# 06_LAN7800.net
KiCad netlist of a schematic drawn in Altium Designer
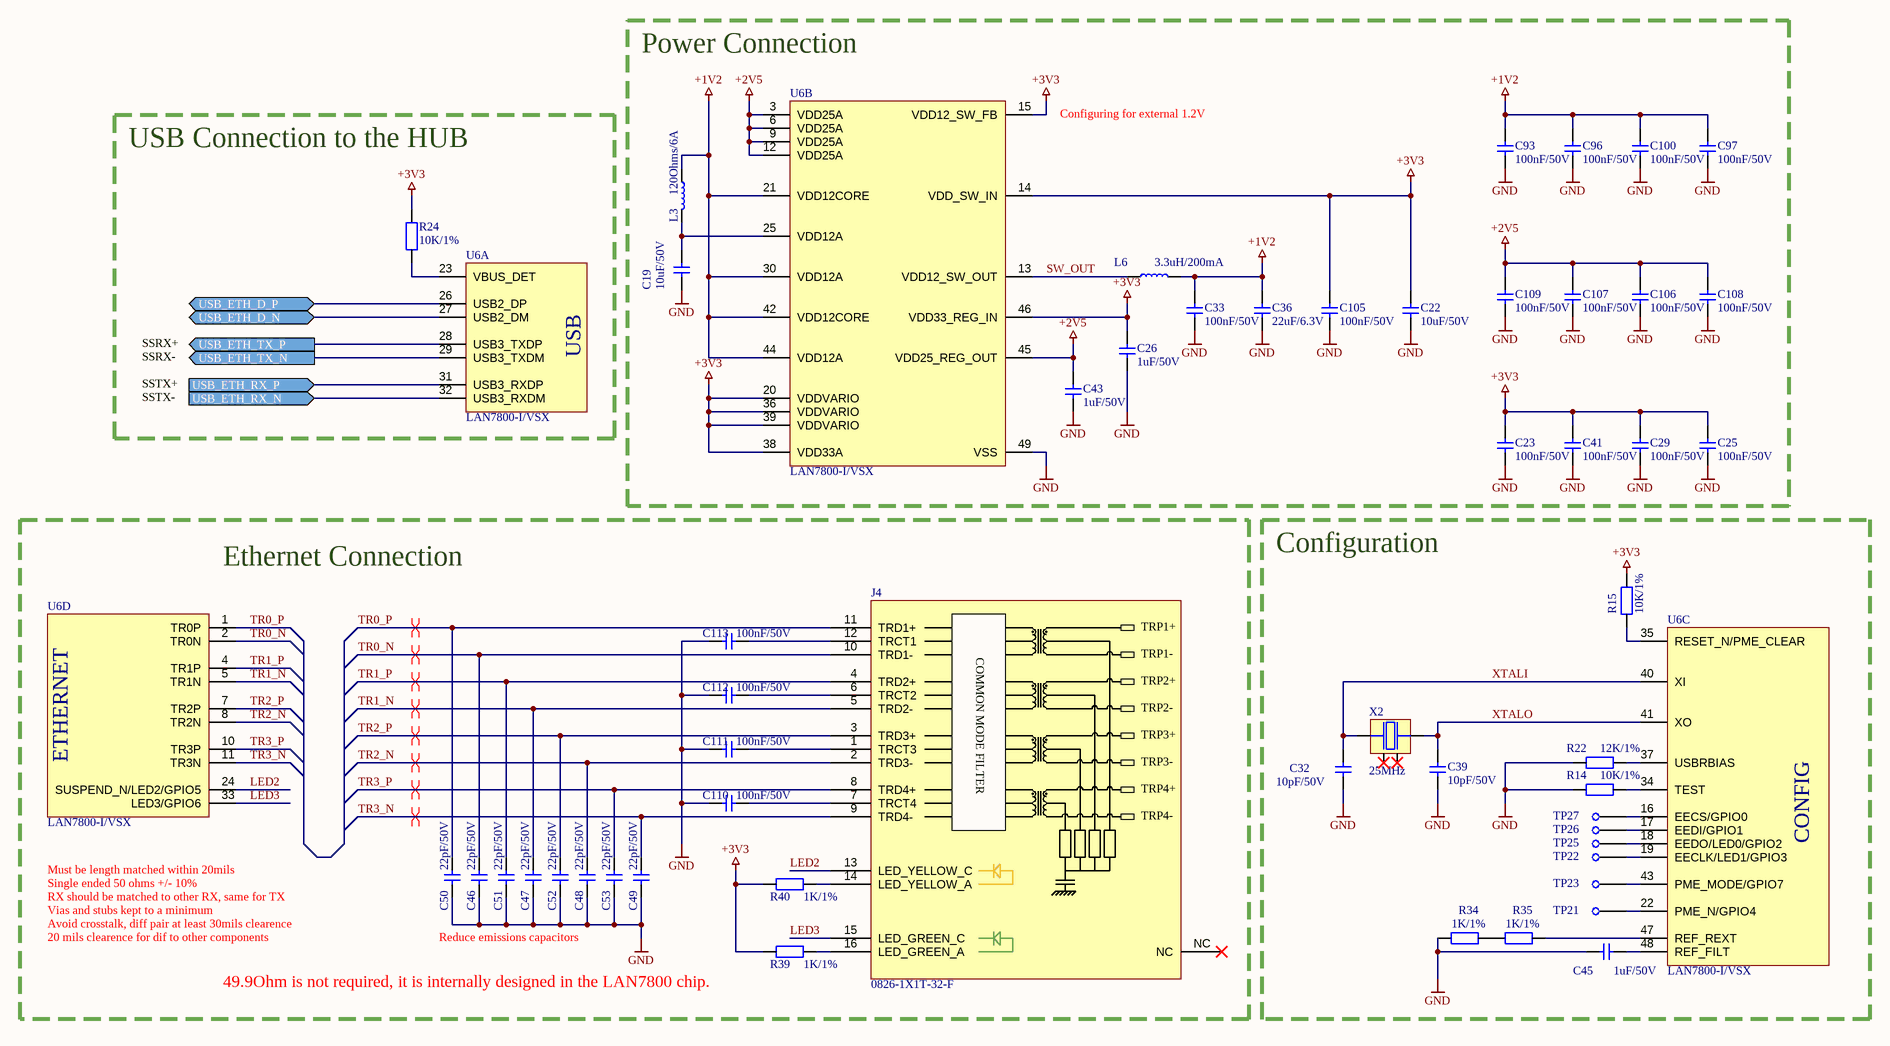
[diagram p0: 06 LAN7800.SchDoc]

(export (version "E")
  (design (tool "Eeschema 10.0.6"))
  (components
    (comp (ref "C19")
      (value "10uF/50V")
      (footprint "CAPC3216X18N")
      (description "10 µF ±20% 50V Ceramic Capacitor X5R 1206 (3216 Metric)")
      (fields
        (field (name "MANUFACTURER") "Murata Electronics")
        (field (name "MFR_PART_NUMBER") "GRT31CR61H106ME01L")
      )
      (libsource (lib "altium_symbol") (part "GRT31CR61H106ME01L"))
    )
    (comp (ref "C22")
      (value "10uF/50V")
      (footprint "CAPC3216X18N")
      (description "10 µF ±20% 50V Ceramic Capacitor X5R 1206 (3216 Metric)")
      (fields
        (field (name "MANUFACTURER") "Murata Electronics")
        (field (name "MFR_PART_NUMBER") "GRT31CR61H106ME01L")
      )
      (libsource (lib "altium_symbol") (part "GRT31CR61H106ME01L"))
    )
    (comp (ref "C23")
      (value "100nF/50V")
      (footprint "CAPC1005X06N")
      (description "0.1 µF ±10% 50V Ceramic Capacitor X7R 0402 (1005 Metric)")
      (fields
        (field (name "MANUFACTURER") "Murata Electronics")
        (field (name "MFR_PART_NUMBER") "GCM155R71H104KE02J")
      )
      (libsource (lib "altium_symbol") (part "GCM155R71H104KE02J"))
    )
    (comp (ref "C25")
      (value "100nF/50V")
      (footprint "CAPC1005X06N")
      (description "0.1 µF ±10% 50V Ceramic Capacitor X7R 0402 (1005 Metric)")
      (fields
        (field (name "MANUFACTURER") "Murata Electronics")
        (field (name "MFR_PART_NUMBER") "GCM155R71H104KE02J")
      )
      (libsource (lib "altium_symbol") (part "GCM155R71H104KE02J"))
    )
    (comp (ref "C26")
      (value "1uF/50V")
      (footprint "INDC1608X10N")
      (description "1 µF ±10% 50V Ceramic Capacitor X5R 0603 (1608 Metric)")
      (fields
        (field (name "MANUFACTURER") "Murata Electronics")
        (field (name "MFR_PART_NUMBER") "GRT188R61H105KE13D")
      )
      (libsource (lib "altium_symbol") (part "GRT188R61H105KE13D"))
    )
    (comp (ref "C29")
      (value "100nF/50V")
      (footprint "CAPC1005X06N")
      (description "0.1 µF ±10% 50V Ceramic Capacitor X7R 0402 (1005 Metric)")
      (fields
        (field (name "MANUFACTURER") "Murata Electronics")
        (field (name "MFR_PART_NUMBER") "GCM155R71H104KE02J")
      )
      (libsource (lib "altium_symbol") (part "GCM155R71H104KE02J"))
    )
    (comp (ref "C32")
      (value "10pF/50V")
      (footprint "CAPC1005X06N")
      (description "10 pF ±5% 50V Ceramic Capacitor C0G, NP0 0402 (1005 Metric)")
      (fields
        (field (name "MANUFACTURER") "Murata Electronics")
        (field (name "MFR_PART_NUMBER") "GCM1555C1H100JA16D")
      )
      (libsource (lib "altium_symbol") (part "GCM1555C1H100JA16D"))
    )
    (comp (ref "C33")
      (value "100nF/50V")
      (footprint "CAPC1005X06N")
      (description "0.1 µF ±10% 50V Ceramic Capacitor X7R 0402 (1005 Metric)")
      (fields
        (field (name "MANUFACTURER") "Murata Electronics")
        (field (name "MFR_PART_NUMBER") "GCM155R71H104KE02J")
      )
      (libsource (lib "altium_symbol") (part "GCM155R71H104KE02J"))
    )
    (comp (ref "C36")
      (value "22uF/6.3V")
      (footprint "INDC1608X10N")
      (description "22 µF ±20% 6.3V Ceramic Capacitor X6S 0603 (1608 Metric)")
      (fields
        (field (name "MANUFACTURER") "Murata Electronics")
        (field (name "MFR_PART_NUMBER") "GRT188C80J226ME13D")
      )
      (libsource (lib "altium_symbol") (part "GRT188C80J226ME13D"))
    )
    (comp (ref "C39")
      (value "10pF/50V")
      (footprint "CAPC1005X06N")
      (description "10 pF ±5% 50V Ceramic Capacitor C0G, NP0 0402 (1005 Metric)")
      (fields
        (field (name "MANUFACTURER") "Murata Electronics")
        (field (name "MFR_PART_NUMBER") "GCM1555C1H100JA16D")
      )
      (libsource (lib "altium_symbol") (part "GCM1555C1H100JA16D"))
    )
    (comp (ref "C41")
      (value "100nF/50V")
      (footprint "CAPC1005X06N")
      (description "0.1 µF ±10% 50V Ceramic Capacitor X7R 0402 (1005 Metric)")
      (fields
        (field (name "MANUFACTURER") "Murata Electronics")
        (field (name "MFR_PART_NUMBER") "GCM155R71H104KE02J")
      )
      (libsource (lib "altium_symbol") (part "GCM155R71H104KE02J"))
    )
    (comp (ref "C43")
      (value "1uF/50V")
      (footprint "INDC1608X10N")
      (description "1 µF ±10% 50V Ceramic Capacitor X5R 0603 (1608 Metric)")
      (fields
        (field (name "MANUFACTURER") "Murata Electronics")
        (field (name "MFR_PART_NUMBER") "GRT188R61H105KE13D")
      )
      (libsource (lib "altium_symbol") (part "GRT188R61H105KE13D"))
    )
    (comp (ref "C45")
      (value "1uF/50V")
      (footprint "INDC1608X10N")
      (description "1 µF ±10% 50V Ceramic Capacitor X5R 0603 (1608 Metric)")
      (fields
        (field (name "MANUFACTURER") "Murata Electronics")
        (field (name "MFR_PART_NUMBER") "GRT188R61H105KE13D")
      )
      (libsource (lib "altium_symbol") (part "GRT188R61H105KE13D"))
    )
    (comp (ref "C46")
      (value "22pF/50V")
      (footprint "CAPC1005X06N")
      (description "22 pF ±5% 50V Ceramic Capacitor C0G, NP0 0402 (1005 Metric)")
      (fields
        (field (name "MANUFACTURER") "Samsung Electro-Mechanics")
        (field (name "MFR_PART_NUMBER") "CL05C220JB51PNC")
      )
      (libsource (lib "altium_symbol") (part "CL05C220JB51PNC"))
    )
    (comp (ref "C47")
      (value "22pF/50V")
      (footprint "CAPC1005X06N")
      (description "22 pF ±5% 50V Ceramic Capacitor C0G, NP0 0402 (1005 Metric)")
      (fields
        (field (name "MANUFACTURER") "Samsung Electro-Mechanics")
        (field (name "MFR_PART_NUMBER") "CL05C220JB51PNC")
      )
      (libsource (lib "altium_symbol") (part "CL05C220JB51PNC"))
    )
    (comp (ref "C48")
      (value "22pF/50V")
      (footprint "CAPC1005X06N")
      (description "22 pF ±5% 50V Ceramic Capacitor C0G, NP0 0402 (1005 Metric)")
      (fields
        (field (name "MANUFACTURER") "Samsung Electro-Mechanics")
        (field (name "MFR_PART_NUMBER") "CL05C220JB51PNC")
      )
      (libsource (lib "altium_symbol") (part "CL05C220JB51PNC"))
    )
    (comp (ref "C49")
      (value "22pF/50V")
      (footprint "CAPC1005X06N")
      (description "22 pF ±5% 50V Ceramic Capacitor C0G, NP0 0402 (1005 Metric)")
      (fields
        (field (name "MANUFACTURER") "Samsung Electro-Mechanics")
        (field (name "MFR_PART_NUMBER") "CL05C220JB51PNC")
      )
      (libsource (lib "altium_symbol") (part "CL05C220JB51PNC"))
    )
    (comp (ref "C50")
      (value "22pF/50V")
      (footprint "CAPC1005X06N")
      (description "22 pF ±5% 50V Ceramic Capacitor C0G, NP0 0402 (1005 Metric)")
      (fields
        (field (name "MANUFACTURER") "Samsung Electro-Mechanics")
        (field (name "MFR_PART_NUMBER") "CL05C220JB51PNC")
      )
      (libsource (lib "altium_symbol") (part "CL05C220JB51PNC"))
    )
    (comp (ref "C51")
      (value "22pF/50V")
      (footprint "CAPC1005X06N")
      (description "22 pF ±5% 50V Ceramic Capacitor C0G, NP0 0402 (1005 Metric)")
      (fields
        (field (name "MANUFACTURER") "Samsung Electro-Mechanics")
        (field (name "MFR_PART_NUMBER") "CL05C220JB51PNC")
      )
      (libsource (lib "altium_symbol") (part "CL05C220JB51PNC"))
    )
    (comp (ref "C52")
      (value "22pF/50V")
      (footprint "CAPC1005X06N")
      (description "22 pF ±5% 50V Ceramic Capacitor C0G, NP0 0402 (1005 Metric)")
      (fields
        (field (name "MANUFACTURER") "Samsung Electro-Mechanics")
        (field (name "MFR_PART_NUMBER") "CL05C220JB51PNC")
      )
      (libsource (lib "altium_symbol") (part "CL05C220JB51PNC"))
    )
    (comp (ref "C53")
      (value "22pF/50V")
      (footprint "CAPC1005X06N")
      (description "22 pF ±5% 50V Ceramic Capacitor C0G, NP0 0402 (1005 Metric)")
      (fields
        (field (name "MANUFACTURER") "Samsung Electro-Mechanics")
        (field (name "MFR_PART_NUMBER") "CL05C220JB51PNC")
      )
      (libsource (lib "altium_symbol") (part "CL05C220JB51PNC"))
    )
    (comp (ref "C93")
      (value "100nF/50V")
      (footprint "CAPC1005X06N")
      (description "0.1 µF ±10% 50V Ceramic Capacitor X7R 0402 (1005 Metric)")
      (fields
        (field (name "MANUFACTURER") "Murata Electronics")
        (field (name "MFR_PART_NUMBER") "GCM155R71H104KE02J")
      )
      (libsource (lib "altium_symbol") (part "GCM155R71H104KE02J"))
    )
    (comp (ref "C96")
      (value "100nF/50V")
      (footprint "CAPC1005X06N")
      (description "0.1 µF ±10% 50V Ceramic Capacitor X7R 0402 (1005 Metric)")
      (fields
        (field (name "MANUFACTURER") "Murata Electronics")
        (field (name "MFR_PART_NUMBER") "GCM155R71H104KE02J")
      )
      (libsource (lib "altium_symbol") (part "GCM155R71H104KE02J"))
    )
    (comp (ref "C97")
      (value "100nF/50V")
      (footprint "CAPC1005X06N")
      (description "0.1 µF ±10% 50V Ceramic Capacitor X7R 0402 (1005 Metric)")
      (fields
        (field (name "MANUFACTURER") "Murata Electronics")
        (field (name "MFR_PART_NUMBER") "GCM155R71H104KE02J")
      )
      (libsource (lib "altium_symbol") (part "GCM155R71H104KE02J"))
    )
    (comp (ref "C100")
      (value "100nF/50V")
      (footprint "CAPC1005X06N")
      (description "0.1 µF ±10% 50V Ceramic Capacitor X7R 0402 (1005 Metric)")
      (fields
        (field (name "MANUFACTURER") "Murata Electronics")
        (field (name "MFR_PART_NUMBER") "GCM155R71H104KE02J")
      )
      (libsource (lib "altium_symbol") (part "GCM155R71H104KE02J"))
    )
    (comp (ref "C105")
      (value "100nF/50V")
      (footprint "CAPC1005X06N")
      (description "0.1 µF ±10% 50V Ceramic Capacitor X7R 0402 (1005 Metric)")
      (fields
        (field (name "MANUFACTURER") "Murata Electronics")
        (field (name "MFR_PART_NUMBER") "GCM155R71H104KE02J")
      )
      (libsource (lib "altium_symbol") (part "GCM155R71H104KE02J"))
    )
    (comp (ref "C106")
      (value "100nF/50V")
      (footprint "CAPC1005X06N")
      (description "0.1 µF ±10% 50V Ceramic Capacitor X7R 0402 (1005 Metric)")
      (fields
        (field (name "MANUFACTURER") "Murata Electronics")
        (field (name "MFR_PART_NUMBER") "GCM155R71H104KE02J")
      )
      (libsource (lib "altium_symbol") (part "GCM155R71H104KE02J"))
    )
    (comp (ref "C107")
      (value "100nF/50V")
      (footprint "CAPC1005X06N")
      (description "0.1 µF ±10% 50V Ceramic Capacitor X7R 0402 (1005 Metric)")
      (fields
        (field (name "MANUFACTURER") "Murata Electronics")
        (field (name "MFR_PART_NUMBER") "GCM155R71H104KE02J")
      )
      (libsource (lib "altium_symbol") (part "GCM155R71H104KE02J"))
    )
    (comp (ref "C108")
      (value "100nF/50V")
      (footprint "CAPC1005X06N")
      (description "0.1 µF ±10% 50V Ceramic Capacitor X7R 0402 (1005 Metric)")
      (fields
        (field (name "MANUFACTURER") "Murata Electronics")
        (field (name "MFR_PART_NUMBER") "GCM155R71H104KE02J")
      )
      (libsource (lib "altium_symbol") (part "GCM155R71H104KE02J"))
    )
    (comp (ref "C109")
      (value "100nF/50V")
      (footprint "CAPC1005X06N")
      (description "0.1 µF ±10% 50V Ceramic Capacitor X7R 0402 (1005 Metric)")
      (fields
        (field (name "MANUFACTURER") "Murata Electronics")
        (field (name "MFR_PART_NUMBER") "GCM155R71H104KE02J")
      )
      (libsource (lib "altium_symbol") (part "GCM155R71H104KE02J"))
    )
    (comp (ref "C110")
      (value "100nF/50V")
      (footprint "CAPC1005X06N")
      (description "0.1 µF ±10% 50V Ceramic Capacitor X7R 0402 (1005 Metric)")
      (fields
        (field (name "MANUFACTURER") "Murata Electronics")
        (field (name "MFR_PART_NUMBER") "GCM155R71H104KE02J")
      )
      (libsource (lib "altium_symbol") (part "GCM155R71H104KE02J"))
    )
    (comp (ref "C111")
      (value "100nF/50V")
      (footprint "CAPC1005X06N")
      (description "0.1 µF ±10% 50V Ceramic Capacitor X7R 0402 (1005 Metric)")
      (fields
        (field (name "MANUFACTURER") "Murata Electronics")
        (field (name "MFR_PART_NUMBER") "GCM155R71H104KE02J")
      )
      (libsource (lib "altium_symbol") (part "GCM155R71H104KE02J"))
    )
    (comp (ref "C112")
      (value "100nF/50V")
      (footprint "CAPC1005X06N")
      (description "0.1 µF ±10% 50V Ceramic Capacitor X7R 0402 (1005 Metric)")
      (fields
        (field (name "MANUFACTURER") "Murata Electronics")
        (field (name "MFR_PART_NUMBER") "GCM155R71H104KE02J")
      )
      (libsource (lib "altium_symbol") (part "GCM155R71H104KE02J"))
    )
    (comp (ref "C113")
      (value "100nF/50V")
      (footprint "CAPC1005X06N")
      (description "0.1 µF ±10% 50V Ceramic Capacitor X7R 0402 (1005 Metric)")
      (fields
        (field (name "MANUFACTURER") "Murata Electronics")
        (field (name "MFR_PART_NUMBER") "GCM155R71H104KE02J")
      )
      (libsource (lib "altium_symbol") (part "GCM155R71H104KE02J"))
    )
    (comp (ref "J4")
      (value "0826-1X1T-32-F")
      (footprint "0826-1X1T-32-F")
      (description "1 Port RJ45Through Hole 10/100/1000 Base-T, AutoMDIX")
      (fields (field (name "MANUFACTURER") "Bel Fuse Inc."))
      (libsource (lib "altium_symbol") (part "0826-1X1T-32-F"))
    )
    (comp (ref "L3")
      (value "120Ohms/6A")
      (footprint "INDC3216X18N")
      (description "120 Ohms @ 100 MHz 1 Power Line Ferrite Bead 1206 (3216 Metric) 6A 9mOhm")
      (fields
        (field (name "MANUFACTURER") "Murata Electronics")
        (field (name "MFR_PART_NUMBER") "BLM31KN121SN1L")
      )
      (libsource (lib "altium_symbol") (part "BLM31KN121SN1L"))
    )
    (comp (ref "L6")
      (value "3.3uH/200mA")
      (footprint "INDP3225X21M")
      (description "3.3 µH Unshielded Drum Core, Wirewound Inductor 200 mA 1.2Ohm Max 2-SMD, J-Lead")
      (fields
        (field (name "MANUFACTURER") "EPCOS - TDK Electronics")
        (field (name "MFR_PART_NUMBER") "B82422A1332J100")
      )
      (libsource (lib "altium_symbol") (part "B82422A1332J100"))
    )
    (comp (ref "R14")
      (value "10K/1%")
      (footprint "RESC1005X04N")
      (description "10 kOhms ±1% 0.063W, 1/16W Chip Resistor 0402 (1005 Metric) Automotive AEC-Q200 Thick Film")
      (fields
        (field (name "MANUFACTURER") "Stackpole Electronics Inc")
        (field (name "MFR_PART_NUMBER") "RMCF0402FT10K0")
      )
      (libsource (lib "altium_symbol") (part "RMCF0402FT10K0"))
    )
    (comp (ref "R15")
      (value "10K/1%")
      (footprint "RESC1005X04N")
      (description "10 kOhms ±1% 0.063W, 1/16W Chip Resistor 0402 (1005 Metric) Automotive AEC-Q200 Thick Film")
      (fields
        (field (name "MANUFACTURER") "Stackpole Electronics Inc")
        (field (name "MFR_PART_NUMBER") "RMCF0402FT10K0")
      )
      (libsource (lib "altium_symbol") (part "RMCF0402FT10K0"))
    )
    (comp (ref "R22")
      (value "12K/1%")
      (footprint "RESC1005X04N")
      (description "12 kOhms ±1% 0.1W, 1/10W Chip Resistor 0402 (1005 Metric) Automotive AEC-Q200 Thick Film")
      (fields
        (field (name "MANUFACTURER") "Panasonic Electronic Components")
        (field (name "MFR_PART_NUMBER") "ERJ-2RKF1202X")
      )
      (libsource (lib "altium_symbol") (part "ERJ-2RKF1202X"))
    )
    (comp (ref "R24")
      (value "10K/1%")
      (footprint "RESC1005X04N")
      (description "10 kOhms ±1% 0.063W, 1/16W Chip Resistor 0402 (1005 Metric) Automotive AEC-Q200 Thick Film")
      (fields
        (field (name "MANUFACTURER") "Stackpole Electronics Inc")
        (field (name "MFR_PART_NUMBER") "RMCF0402FT10K0")
      )
      (libsource (lib "altium_symbol") (part "RMCF0402FT10K0"))
    )
    (comp (ref "R34")
      (value "1K/1%")
      (footprint "RESC1005X04N")
      (description "1 kOhms ±1% 0.063W, 1/16W Chip Resistor 0402 (1005 Metric) Automotive AEC-Q200 Thick Film")
      (fields
        (field (name "MANUFACTURER") "Stackpole Electronics Inc")
        (field (name "MFR_PART_NUMBER") "RMCF0402FT1K00")
      )
      (libsource (lib "altium_symbol") (part "RMCF0402FT1K00"))
    )
    (comp (ref "R35")
      (value "1K/1%")
      (footprint "RESC1005X04N")
      (description "1 kOhms ±1% 0.063W, 1/16W Chip Resistor 0402 (1005 Metric) Automotive AEC-Q200 Thick Film")
      (fields
        (field (name "MANUFACTURER") "Stackpole Electronics Inc")
        (field (name "MFR_PART_NUMBER") "RMCF0402FT1K00")
      )
      (libsource (lib "altium_symbol") (part "RMCF0402FT1K00"))
    )
    (comp (ref "R39")
      (value "1K/1%")
      (footprint "RESC1005X04N")
      (description "1 kOhms ±1% 0.063W, 1/16W Chip Resistor 0402 (1005 Metric) Automotive AEC-Q200 Thick Film")
      (fields
        (field (name "MANUFACTURER") "Stackpole Electronics Inc")
        (field (name "MFR_PART_NUMBER") "RMCF0402FT1K00")
      )
      (libsource (lib "altium_symbol") (part "RMCF0402FT1K00"))
    )
    (comp (ref "R40")
      (value "1K/1%")
      (footprint "RESC1005X04N")
      (description "1 kOhms ±1% 0.063W, 1/16W Chip Resistor 0402 (1005 Metric) Automotive AEC-Q200 Thick Film")
      (fields
        (field (name "MANUFACTURER") "Stackpole Electronics Inc")
        (field (name "MFR_PART_NUMBER") "RMCF0402FT1K00")
      )
      (libsource (lib "altium_symbol") (part "RMCF0402FT1K00"))
    )
    (comp (ref "TP21")
      (value "Test Point 1mm")
      (footprint "TEST_POINT_1mm")
      (libsource (lib "altium_symbol") (part "TestPoint"))
    )
    (comp (ref "TP22")
      (value "Test Point 1mm")
      (footprint "TEST_POINT_1mm")
      (libsource (lib "altium_symbol") (part "TestPoint"))
    )
    (comp (ref "TP23")
      (value "Test Point 1mm")
      (footprint "TEST_POINT_1mm")
      (libsource (lib "altium_symbol") (part "TestPoint"))
    )
    (comp (ref "TP25")
      (value "Test Point 1mm")
      (footprint "TEST_POINT_1mm")
      (libsource (lib "altium_symbol") (part "TestPoint"))
    )
    (comp (ref "TP26")
      (value "Test Point 1mm")
      (footprint "TEST_POINT_1mm")
      (libsource (lib "altium_symbol") (part "TestPoint"))
    )
    (comp (ref "TP27")
      (value "Test Point 1mm")
      (footprint "TEST_POINT_1mm")
      (libsource (lib "altium_symbol") (part "TestPoint"))
    )
    (comp (ref "U6")
      (value "LAN7800-I/VSX")
      (footprint "PQFN40P600X600X90_HS-49N")
      (description "Ethernet Controller 10/100/1000 Base-TX PHY Interface 48-SQFN (6x6)")
      (fields (field (name "MANUFACTURER") "Microchip Technology"))
      (libsource (lib "altium_symbol") (part "LAN7800-I/VSX"))
    )
    (comp (ref "X2")
      (value "25MHz")
      (footprint "XRCGB25M000F3M00R0")
      (description "25 MHz ±30ppm Crystal 6pF 150 Ohms 4-SMD, No Lead")
      (fields
        (field (name "MANUFACTURER") "Murata Electronics")
        (field (name "MFR_PART_NUMBER") "XRCGB25M000F3M00R0")
      )
      (libsource (lib "altium_symbol") (part "XRCGB25M000F3M00R0"))
    )
  )
  (nets
    (net (code "1") (name "+1V2") (class "Default")
      (node (ref "C100") (pin "1") (pinfunction "1_1") (pintype "passive"))
      (node (ref "C33") (pin "1") (pinfunction "1_1") (pintype "passive"))
      (node (ref "C36") (pin "2") (pinfunction "2_2") (pintype "passive"))
      (node (ref "C93") (pin "1") (pinfunction "1_1") (pintype "passive"))
      (node (ref "C96") (pin "1") (pinfunction "1_1") (pintype "passive"))
      (node (ref "C97") (pin "1") (pinfunction "1_1") (pintype "passive"))
      (node (ref "L3") (pin "1") (pinfunction "1_1") (pintype "passive"))
      (node (ref "L6") (pin "2") (pinfunction "2_2") (pintype "passive"))
      (node (ref "U6") (pin "21") (pinfunction "VDD12CORE_21") (pintype "passive"))
      (node (ref "U6") (pin "30") (pinfunction "VDD12A_30") (pintype "passive"))
      (node (ref "U6") (pin "42") (pinfunction "VDD12CORE_42") (pintype "passive"))
      (node (ref "U6") (pin "44") (pinfunction "VDD12A_44") (pintype "passive"))
    )
    (net (code "2") (name "+2V5") (class "Default")
      (node (ref "C106") (pin "1") (pinfunction "1_1") (pintype "passive"))
      (node (ref "C107") (pin "1") (pinfunction "1_1") (pintype "passive"))
      (node (ref "C108") (pin "1") (pinfunction "1_1") (pintype "passive"))
      (node (ref "C109") (pin "1") (pinfunction "1_1") (pintype "passive"))
      (node (ref "C43") (pin "2") (pinfunction "2_2") (pintype "passive"))
      (node (ref "U6") (pin "12") (pinfunction "VDD25A_12") (pintype "passive"))
      (node (ref "U6") (pin "3") (pinfunction "VDD25A_3") (pintype "passive"))
      (node (ref "U6") (pin "45") (pinfunction "VDD25_REG_OUT_45") (pintype "passive"))
      (node (ref "U6") (pin "6") (pinfunction "VDD25A_6") (pintype "passive"))
      (node (ref "U6") (pin "9") (pinfunction "VDD25A_9") (pintype "passive"))
    )
    (net (code "3") (name "+3V3") (class "Default")
      (node (ref "C105") (pin "1") (pinfunction "1_1") (pintype "passive"))
      (node (ref "C22") (pin "2") (pinfunction "2_2") (pintype "passive"))
      (node (ref "C23") (pin "1") (pinfunction "1_1") (pintype "passive"))
      (node (ref "C25") (pin "1") (pinfunction "1_1") (pintype "passive"))
      (node (ref "C26") (pin "2") (pinfunction "2_2") (pintype "passive"))
      (node (ref "C29") (pin "1") (pinfunction "1_1") (pintype "passive"))
      (node (ref "C41") (pin "1") (pinfunction "1_1") (pintype "passive"))
      (node (ref "R15") (pin "1") (pinfunction "1_1") (pintype "passive"))
      (node (ref "R24") (pin "1") (pinfunction "1_1") (pintype "passive"))
      (node (ref "R39") (pin "2") (pinfunction "2_2") (pintype "passive"))
      (node (ref "R40") (pin "2") (pinfunction "2_2") (pintype "passive"))
      (node (ref "U6") (pin "14") (pinfunction "VDD_SW_IN_14") (pintype "passive"))
      (node (ref "U6") (pin "15") (pinfunction "VDD12_SW_FB_15") (pintype "passive"))
      (node (ref "U6") (pin "20") (pinfunction "VDDVARIO_20") (pintype "passive"))
      (node (ref "U6") (pin "36") (pinfunction "VDDVARIO_36") (pintype "passive"))
      (node (ref "U6") (pin "38") (pinfunction "VDD33A_38") (pintype "passive"))
      (node (ref "U6") (pin "39") (pinfunction "VDDVARIO_39") (pintype "passive"))
      (node (ref "U6") (pin "46") (pinfunction "VDD33_REG_IN_46") (pintype "passive"))
    )
    (net (code "4") (name "/LED2") (class "Default")
      (node (ref "J4") (pin "13") (pinfunction "LED_YELLOW_C_13") (pintype "passive"))
      (node (ref "U6") (pin "24") (pinfunction "SUSPEND_N/LED2/GPIO5_24") (pintype "passive"))
    )
    (net (code "5") (name "/LED3") (class "Default")
      (node (ref "J4") (pin "15") (pinfunction "LED_GREEN_C_15") (pintype "passive"))
      (node (ref "U6") (pin "33") (pinfunction "LED3/GPIO6_33") (pintype "passive"))
    )
    (net (code "6") (name "/SW_OUT") (class "Default")
      (node (ref "L6") (pin "1") (pinfunction "1_1") (pintype "passive"))
      (node (ref "U6") (pin "13") (pinfunction "VDD12_SW_OUT_13") (pintype "passive"))
    )
    (net (code "7") (name "/TR0_N") (class "Default")
      (node (ref "C46") (pin "2") (pinfunction "2_2") (pintype "passive"))
      (node (ref "J4") (pin "10") (pinfunction "TRD1-_10") (pintype "passive"))
      (node (ref "U6") (pin "2") (pinfunction "TR0N_2") (pintype "passive"))
    )
    (net (code "8") (name "/TR0_P") (class "Default")
      (node (ref "C50") (pin "2") (pinfunction "2_2") (pintype "passive"))
      (node (ref "J4") (pin "11") (pinfunction "TRD1+_11") (pintype "passive"))
      (node (ref "U6") (pin "1") (pinfunction "TR0P_1") (pintype "passive"))
    )
    (net (code "9") (name "/TR1_N") (class "Default")
      (node (ref "C47") (pin "2") (pinfunction "2_2") (pintype "passive"))
      (node (ref "J4") (pin "5") (pinfunction "TRD2-_5") (pintype "passive"))
      (node (ref "U6") (pin "5") (pinfunction "TR1N_5") (pintype "passive"))
    )
    (net (code "10") (name "/TR1_P") (class "Default")
      (node (ref "C51") (pin "2") (pinfunction "2_2") (pintype "passive"))
      (node (ref "J4") (pin "4") (pinfunction "TRD2+_4") (pintype "passive"))
      (node (ref "U6") (pin "4") (pinfunction "TR1P_4") (pintype "passive"))
    )
    (net (code "11") (name "/TR2_N") (class "Default")
      (node (ref "C48") (pin "2") (pinfunction "2_2") (pintype "passive"))
      (node (ref "J4") (pin "2") (pinfunction "TRD3-_2") (pintype "passive"))
      (node (ref "U6") (pin "8") (pinfunction "TR2N_8") (pintype "passive"))
    )
    (net (code "12") (name "/TR2_P") (class "Default")
      (node (ref "C52") (pin "2") (pinfunction "2_2") (pintype "passive"))
      (node (ref "J4") (pin "3") (pinfunction "TRD3+_3") (pintype "passive"))
      (node (ref "U6") (pin "7") (pinfunction "TR2P_7") (pintype "passive"))
    )
    (net (code "13") (name "/TR3_N") (class "Default")
      (node (ref "C49") (pin "2") (pinfunction "2_2") (pintype "passive"))
      (node (ref "J4") (pin "9") (pinfunction "TRD4-_9") (pintype "passive"))
      (node (ref "U6") (pin "11") (pinfunction "TR3N_11") (pintype "passive"))
    )
    (net (code "14") (name "/TR3_P") (class "Default")
      (node (ref "C53") (pin "2") (pinfunction "2_2") (pintype "passive"))
      (node (ref "J4") (pin "8") (pinfunction "TRD4+_8") (pintype "passive"))
      (node (ref "U6") (pin "10") (pinfunction "TR3P_10") (pintype "passive"))
    )
    (net (code "15") (name "/USB_ETH_D_N") (class "Default")
      (node (ref "U6") (pin "27") (pinfunction "USB2_DM_27") (pintype "passive"))
    )
    (net (code "16") (name "/USB_ETH_D_P") (class "Default")
      (node (ref "U6") (pin "26") (pinfunction "USB2_DP_26") (pintype "passive"))
    )
    (net (code "17") (name "/USB_ETH_RX_N") (class "Default")
      (node (ref "U6") (pin "32") (pinfunction "USB3_RXDM_32") (pintype "passive"))
    )
    (net (code "18") (name "/USB_ETH_RX_P") (class "Default")
      (node (ref "U6") (pin "31") (pinfunction "USB3_RXDP_31") (pintype "passive"))
    )
    (net (code "19") (name "/USB_ETH_TX_N") (class "Default")
      (node (ref "U6") (pin "29") (pinfunction "USB3_TXDM_29") (pintype "passive"))
    )
    (net (code "20") (name "/USB_ETH_TX_P") (class "Default")
      (node (ref "U6") (pin "28") (pinfunction "USB3_TXDP_28") (pintype "passive"))
    )
    (net (code "21") (name "/XTALI") (class "Default")
      (node (ref "C32") (pin "2") (pinfunction "2_2") (pintype "passive"))
      (node (ref "U6") (pin "40") (pinfunction "XI_40") (pintype "passive"))
      (node (ref "X2") (pin "3") (pinfunction "3_3") (pintype "passive"))
    )
    (net (code "22") (name "/XTALO") (class "Default")
      (node (ref "C39") (pin "2") (pinfunction "2_2") (pintype "passive"))
      (node (ref "U6") (pin "41") (pinfunction "XO_41") (pintype "passive"))
      (node (ref "X2") (pin "1") (pinfunction "1_1") (pintype "passive"))
    )
    (net (code "23") (name "GND") (class "Default")
      (node (ref "C100") (pin "2") (pinfunction "2_2") (pintype "passive"))
      (node (ref "C105") (pin "2") (pinfunction "2_2") (pintype "passive"))
      (node (ref "C106") (pin "2") (pinfunction "2_2") (pintype "passive"))
      (node (ref "C107") (pin "2") (pinfunction "2_2") (pintype "passive"))
      (node (ref "C108") (pin "2") (pinfunction "2_2") (pintype "passive"))
      (node (ref "C109") (pin "2") (pinfunction "2_2") (pintype "passive"))
      (node (ref "C110") (pin "2") (pinfunction "2_2") (pintype "passive"))
      (node (ref "C111") (pin "2") (pinfunction "2_2") (pintype "passive"))
      (node (ref "C112") (pin "2") (pinfunction "2_2") (pintype "passive"))
      (node (ref "C113") (pin "2") (pinfunction "2_2") (pintype "passive"))
      (node (ref "C19") (pin "1") (pinfunction "1_1") (pintype "passive"))
      (node (ref "C22") (pin "1") (pinfunction "1_1") (pintype "passive"))
      (node (ref "C23") (pin "2") (pinfunction "2_2") (pintype "passive"))
      (node (ref "C25") (pin "2") (pinfunction "2_2") (pintype "passive"))
      (node (ref "C26") (pin "1") (pinfunction "1_1") (pintype "passive"))
      (node (ref "C29") (pin "2") (pinfunction "2_2") (pintype "passive"))
      (node (ref "C32") (pin "1") (pinfunction "1_1") (pintype "passive"))
      (node (ref "C33") (pin "2") (pinfunction "2_2") (pintype "passive"))
      (node (ref "C36") (pin "1") (pinfunction "1_1") (pintype "passive"))
      (node (ref "C39") (pin "1") (pinfunction "1_1") (pintype "passive"))
      (node (ref "C41") (pin "2") (pinfunction "2_2") (pintype "passive"))
      (node (ref "C43") (pin "1") (pinfunction "1_1") (pintype "passive"))
      (node (ref "C45") (pin "2") (pinfunction "2_2") (pintype "passive"))
      (node (ref "C46") (pin "1") (pinfunction "1_1") (pintype "passive"))
      (node (ref "C47") (pin "1") (pinfunction "1_1") (pintype "passive"))
      (node (ref "C48") (pin "1") (pinfunction "1_1") (pintype "passive"))
      (node (ref "C49") (pin "1") (pinfunction "1_1") (pintype "passive"))
      (node (ref "C50") (pin "1") (pinfunction "1_1") (pintype "passive"))
      (node (ref "C51") (pin "1") (pinfunction "1_1") (pintype "passive"))
      (node (ref "C52") (pin "1") (pinfunction "1_1") (pintype "passive"))
      (node (ref "C53") (pin "1") (pinfunction "1_1") (pintype "passive"))
      (node (ref "C93") (pin "2") (pinfunction "2_2") (pintype "passive"))
      (node (ref "C96") (pin "2") (pinfunction "2_2") (pintype "passive"))
      (node (ref "C97") (pin "2") (pinfunction "2_2") (pintype "passive"))
      (node (ref "R14") (pin "1") (pinfunction "1_1") (pintype "passive"))
      (node (ref "R22") (pin "2") (pinfunction "2_2") (pintype "passive"))
      (node (ref "R34") (pin "1") (pinfunction "1_1") (pintype "passive"))
      (node (ref "U6") (pin "49") (pinfunction "VSS_49") (pintype "passive"))
    )
    (net (code "24") (name "Net-(C19-Pad2)") (class "Default")
      (node (ref "C19") (pin "2") (pinfunction "2_2") (pintype "passive"))
      (node (ref "L3") (pin "2") (pinfunction "2_2") (pintype "passive"))
      (node (ref "U6") (pin "25") (pinfunction "VDD12A_25") (pintype "passive"))
    )
    (net (code "25") (name "Net-(J4-LED_GREEN_A)") (class "Default")
      (node (ref "J4") (pin "16") (pinfunction "LED_GREEN_A_16") (pintype "passive"))
      (node (ref "R39") (pin "1") (pinfunction "1_1") (pintype "passive"))
    )
    (net (code "26") (name "Net-(J4-LED_YELLOW_A)") (class "Default")
      (node (ref "J4") (pin "14") (pinfunction "LED_YELLOW_A_14") (pintype "passive"))
      (node (ref "R40") (pin "1") (pinfunction "1_1") (pintype "passive"))
    )
    (net (code "27") (name "Net-(J4-TRCT1)") (class "Default")
      (node (ref "C113") (pin "1") (pinfunction "1_1") (pintype "passive"))
      (node (ref "J4") (pin "12") (pinfunction "TRCT1_12") (pintype "passive"))
    )
    (net (code "28") (name "Net-(J4-TRCT2)") (class "Default")
      (node (ref "C112") (pin "1") (pinfunction "1_1") (pintype "passive"))
      (node (ref "J4") (pin "6") (pinfunction "TRCT2_6") (pintype "passive"))
    )
    (net (code "29") (name "Net-(J4-TRCT3)") (class "Default")
      (node (ref "C111") (pin "1") (pinfunction "1_1") (pintype "passive"))
      (node (ref "J4") (pin "1") (pinfunction "TRCT3_1") (pintype "passive"))
    )
    (net (code "30") (name "Net-(J4-TRCT4)") (class "Default")
      (node (ref "C110") (pin "1") (pinfunction "1_1") (pintype "passive"))
      (node (ref "J4") (pin "7") (pinfunction "TRCT4_7") (pintype "passive"))
    )
    (net (code "31") (name "Net-(R34-Pad2)") (class "Default")
      (node (ref "R34") (pin "2") (pinfunction "2_2") (pintype "passive"))
      (node (ref "R35") (pin "1") (pinfunction "1_1") (pintype "passive"))
    )
    (net (code "32") (name "Net-(U6A-VBUS_DET)") (class "Default")
      (node (ref "R24") (pin "2") (pinfunction "2_2") (pintype "passive"))
      (node (ref "U6") (pin "23") (pinfunction "VBUS_DET_23") (pintype "passive"))
    )
    (net (code "33") (name "Net-(U6C-EECLK{slash}LED1{slash}GPIO3)") (class "Default")
      (node (ref "TP22") (pin "1") (pinfunction "1_1") (pintype "passive"))
      (node (ref "U6") (pin "19") (pinfunction "EECLK/LED1/GPIO3_19") (pintype "passive"))
    )
    (net (code "34") (name "Net-(U6C-EECS{slash}GPIO0)") (class "Default")
      (node (ref "TP27") (pin "1") (pinfunction "1_1") (pintype "passive"))
      (node (ref "U6") (pin "16") (pinfunction "EECS/GPIO0_16") (pintype "passive"))
    )
    (net (code "35") (name "Net-(U6C-EEDI{slash}GPIO1)") (class "Default")
      (node (ref "TP26") (pin "1") (pinfunction "1_1") (pintype "passive"))
      (node (ref "U6") (pin "17") (pinfunction "EEDI/GPIO1_17") (pintype "passive"))
    )
    (net (code "36") (name "Net-(U6C-EEDO{slash}LED0{slash}GPIO2)") (class "Default")
      (node (ref "TP25") (pin "1") (pinfunction "1_1") (pintype "passive"))
      (node (ref "U6") (pin "18") (pinfunction "EEDO/LED0/GPIO2_18") (pintype "passive"))
    )
    (net (code "37") (name "Net-(U6C-PME_MODE{slash}GPIO7)") (class "Default")
      (node (ref "TP23") (pin "1") (pinfunction "1_1") (pintype "passive"))
      (node (ref "U6") (pin "43") (pinfunction "PME_MODE/GPIO7_43") (pintype "passive"))
    )
    (net (code "38") (name "Net-(U6C-PME_N{slash}GPIO4)") (class "Default")
      (node (ref "TP21") (pin "1") (pinfunction "1_1") (pintype "passive"))
      (node (ref "U6") (pin "22") (pinfunction "PME_N/GPIO4_22") (pintype "passive"))
    )
    (net (code "39") (name "Net-(U6C-REF_FILT)") (class "Default")
      (node (ref "C45") (pin "1") (pinfunction "1_1") (pintype "passive"))
      (node (ref "U6") (pin "48") (pinfunction "REF_FILT_48") (pintype "passive"))
    )
    (net (code "40") (name "Net-(U6C-REF_REXT)") (class "Default")
      (node (ref "R35") (pin "2") (pinfunction "2_2") (pintype "passive"))
      (node (ref "U6") (pin "47") (pinfunction "REF_REXT_47") (pintype "passive"))
    )
    (net (code "41") (name "Net-(U6C-RESET_N{slash}PME_CLEAR)") (class "Default")
      (node (ref "R15") (pin "2") (pinfunction "2_2") (pintype "passive"))
      (node (ref "U6") (pin "35") (pinfunction "RESET_N/PME_CLEAR_35") (pintype "passive"))
    )
    (net (code "42") (name "Net-(U6C-TEST)") (class "Default")
      (node (ref "R14") (pin "2") (pinfunction "2_2") (pintype "passive"))
      (node (ref "U6") (pin "34") (pinfunction "TEST_34") (pintype "passive"))
    )
    (net (code "43") (name "Net-(U6C-USBRBIAS)") (class "Default")
      (node (ref "R22") (pin "1") (pinfunction "1_1") (pintype "passive"))
      (node (ref "U6") (pin "37") (pinfunction "USBRBIAS_37") (pintype "passive"))
    )
    (net (code "44") (name "unconnected-(J4-PadNC)") (class "Default")
      (node (ref "J4") (pin "NC") (pinfunction "NC_NC") (pintype "passive+no_connect"))
    )
    (net (code "45") (name "unconnected-(X2-Pad2)") (class "Default")
      (node (ref "X2") (pin "2") (pinfunction "2_2") (pintype "passive+no_connect"))
    )
    (net (code "46") (name "unconnected-(X2-Pad4)") (class "Default")
      (node (ref "X2") (pin "4") (pinfunction "4_4") (pintype "passive+no_connect"))
    )
  )
)
